# Schematic.net
KiCad netlist of a schematic drawn in Altium Designer
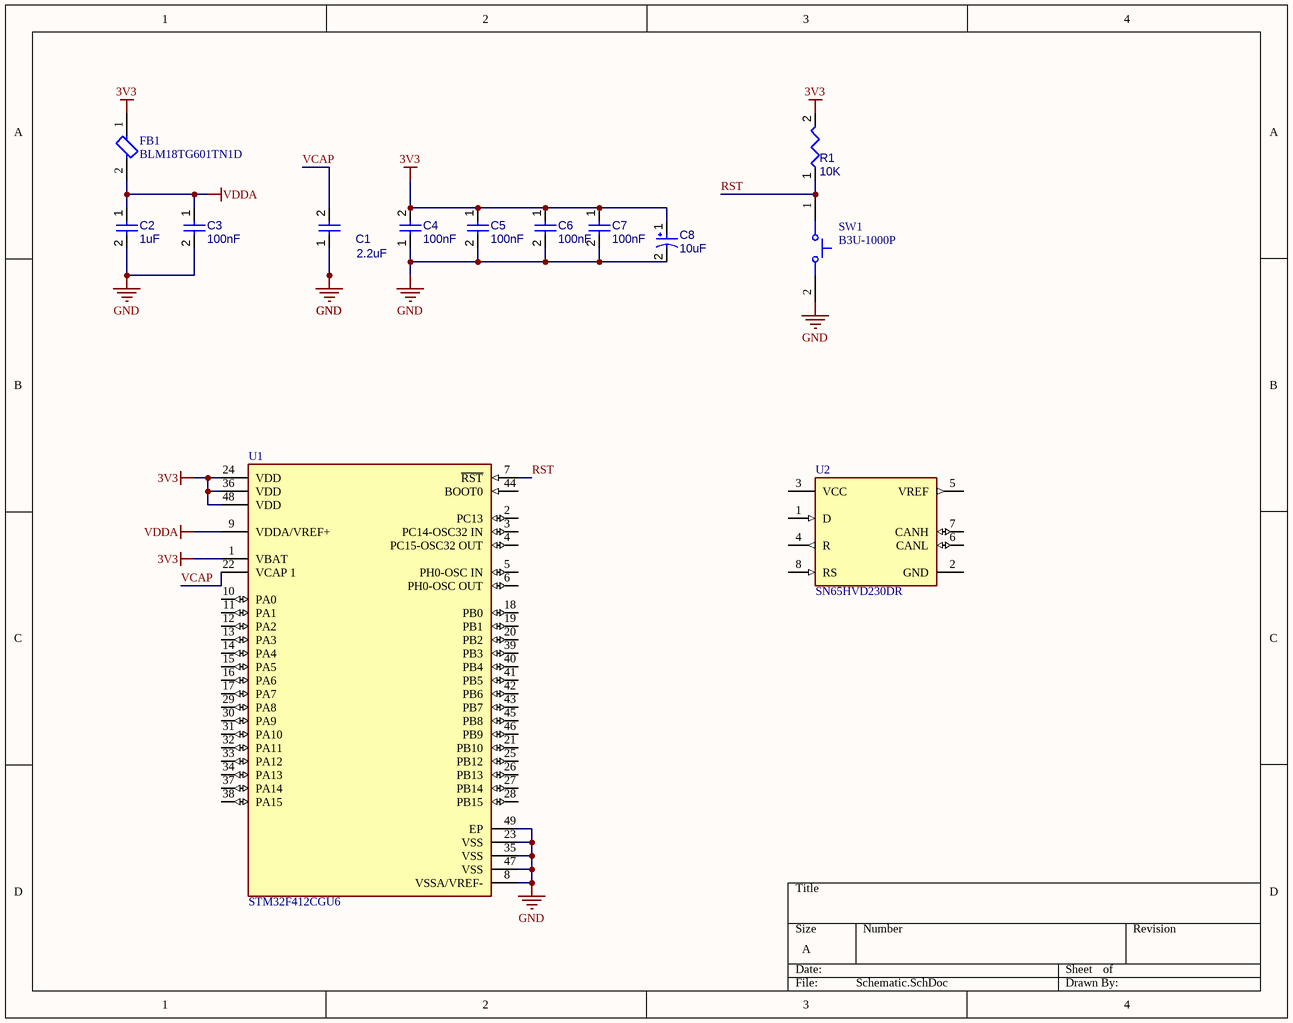
[diagram p0: Schematic.SchDoc]

(export (version "E")
  (design (tool "Eeschema 10.0.6"))
  (components
    (comp (ref "C1")
      (value "2.2uF")
      (footprint "CAPC0402(1005)60_L")
      (description "Chip Capacitor, 2,2µF +/-20%, 10V, 0402, Thickness 0.6 mm")
      (fields (field (name "TOLERANCE") "10%"))
      (libsource (lib "Bronco Racing") (part "CAP-NP-2"))
    )
    (comp (ref "C2")
      (value "1uF")
      (footprint "CAPC0402(1005)60_L")
      (description "Chip Capacitor, 1µF +/-20%, 10V, 0402, Thickness 0.6 mm")
      (fields (field (name "TOLERANCE") "10%"))
      (libsource (lib "Bronco Racing") (part "CAP-NP-2"))
    )
    (comp (ref "C3")
      (value "100nF")
      (footprint "CAPC0402(1005)60_L")
      (description "Chip Capacitor, 100nF +/-20%, 10V, 0402, Thickness 0.6 mm")
      (fields (field (name "TOLERANCE") "20%"))
      (libsource (lib "Bronco Racing") (part "CAP-NP-2"))
    )
    (comp (ref "C4")
      (value "100nF")
      (footprint "CAPC0402(1005)60_L")
      (description "Chip Capacitor, 100nF +/-20%, 10V, 0402, Thickness 0.6 mm")
      (fields (field (name "TOLERANCE") "20%"))
      (libsource (lib "Bronco Racing") (part "CAP-NP-2"))
    )
    (comp (ref "C5")
      (value "100nF")
      (footprint "CAPC0402(1005)60_L")
      (description "Chip Capacitor, 100nF +/-20%, 10V, 0402, Thickness 0.6 mm")
      (fields (field (name "TOLERANCE") "20%"))
      (libsource (lib "Bronco Racing") (part "CAP-NP-2"))
    )
    (comp (ref "C6")
      (value "100nF")
      (footprint "CAPC0402(1005)60_L")
      (description "Chip Capacitor, 100nF +/-20%, 10V, 0402, Thickness 0.6 mm")
      (fields (field (name "TOLERANCE") "20%"))
      (libsource (lib "Bronco Racing") (part "CAP-NP-2"))
    )
    (comp (ref "C7")
      (value "100nF")
      (footprint "CAPC0402(1005)60_L")
      (description "Chip Capacitor, 100nF +/-20%, 10V, 0402, Thickness 0.6 mm")
      (fields (field (name "TOLERANCE") "20%"))
      (libsource (lib "Bronco Racing") (part "CAP-NP-2"))
    )
    (comp (ref "C8")
      (value "10uF")
      (footprint "CAPMP3217X18-T_V")
      (description "Standard Tantalum, 10 uF, +/- 10%, 16 V, -55 to 125 degC, 1206 (3216 Metric), RoHS, Tape and Reel")
      (fields (field (name "TOLERANCE") "10%") (field (name "MANUFACTURER") "AVX"))
      (libsource (lib "Bronco Racing") (part "CAP-P-2"))
    )
    (comp (ref "FB1")
      (value "BLM18TG601TN1D")
      (footprint "FP-BLM18-0_15-0_1-t0_6-MFG")
      (description "FERRITE BEAD 600 OHM 0603 1LN")
      (fields (field (name "TOLERANCE") "25%"))
      (libsource (lib "Altium Content Vault") (part "5f30dd21d616792df468990f7003faa"))
    )
    (comp (ref "R1")
      (value "10K")
      (footprint "RESC0402(1005)_L")
      (description "Chip Resistor, 10 kOhms, +/-1 %, 63 mW, -55 to 125 degC, 0402")
      (fields (field (name "POWER") "63mW") (field (name "TOLERANCE") "1%"))
      (libsource (lib "Bronco Racing") (part "RES-2"))
    )
    (comp (ref "SW1")
      (value "B3U-1000P")
      (footprint "OMRON-B3U-1000_V")
      (description "Tactile Switch, SPST-NO, 0.05 A, 12 V, -25 to 70 degC, 2-Pin SMD, RoHS, Tape and Reel")
      (fields (field (name "MANUFACTURER") "Omron Electronic Components"))
      (libsource (lib "Bronco Racing") (part "SW-SPST-NO-2"))
    )
    (comp (ref "U1")
      (value "STM32F412CGU6")
      (footprint "FP-UFQFPN48-A0B9-MFG")
      (description "IC MCU 32BIT 1MB FLASH 48UFQFPN")
      (libsource (lib "Altium Content Vault") (part "7dd92b861eb4b166e7106aa1111722c"))
    )
    (comp (ref "U2")
      (value "SN65HVD230DR")
      (footprint "FP-D0008A-IPC_A")
      (description "IC TRANSCEIVER HALF 1/1 8SOIC")
      (libsource (lib "Altium Content Vault") (part "43b56812b1adf0e60a7acfb7c27ab91"))
    )
  )
  (nets
    (net (code "1") (name "/RST") (class "Default")
      (node (ref "R1") (pin "1") (pinfunction "1_1") (pintype "passive"))
      (node (ref "SW1") (pin "1") (pinfunction "1_1") (pintype "passive"))
      (node (ref "U1") (pin "7") (pinfunction "~{RST}_7") (pintype "input"))
    )
    (net (code "2") (name "/VCAP") (class "Default")
      (node (ref "C1") (pin "2") (pinfunction "2_2") (pintype "passive"))
      (node (ref "U1") (pin "22") (pinfunction "VCAP_1_22") (pintype "power_in"))
    )
    (net (code "3") (name "3V3") (class "Default")
      (node (ref "C4") (pin "2") (pinfunction "2_2") (pintype "passive"))
      (node (ref "C5") (pin "1") (pinfunction "1_1") (pintype "passive"))
      (node (ref "C6") (pin "1") (pinfunction "1_1") (pintype "passive"))
      (node (ref "C7") (pin "1") (pinfunction "1_1") (pintype "passive"))
      (node (ref "C8") (pin "1") (pinfunction "1_1") (pintype "passive"))
      (node (ref "FB1") (pin "1") (pinfunction "1_1") (pintype "passive"))
      (node (ref "R1") (pin "2") (pinfunction "2_2") (pintype "passive"))
      (node (ref "U1") (pin "1") (pinfunction "VBAT_1") (pintype "power_in"))
      (node (ref "U1") (pin "24") (pinfunction "VDD_24") (pintype "power_in"))
      (node (ref "U1") (pin "36") (pinfunction "VDD_36") (pintype "power_in"))
      (node (ref "U1") (pin "48") (pinfunction "VDD_48") (pintype "power_in"))
    )
    (net (code "4") (name "GND") (class "Default")
      (node (ref "C1") (pin "1") (pinfunction "1_1") (pintype "passive"))
      (node (ref "C2") (pin "2") (pinfunction "2_2") (pintype "passive"))
      (node (ref "C3") (pin "2") (pinfunction "2_2") (pintype "passive"))
      (node (ref "C4") (pin "1") (pinfunction "1_1") (pintype "passive"))
      (node (ref "C5") (pin "2") (pinfunction "2_2") (pintype "passive"))
      (node (ref "C6") (pin "2") (pinfunction "2_2") (pintype "passive"))
      (node (ref "C7") (pin "2") (pinfunction "2_2") (pintype "passive"))
      (node (ref "C8") (pin "2") (pinfunction "2_2") (pintype "passive"))
      (node (ref "SW1") (pin "2") (pinfunction "2_2") (pintype "passive"))
      (node (ref "U1") (pin "23") (pinfunction "VSS_23") (pintype "power_in"))
      (node (ref "U1") (pin "35") (pinfunction "VSS_35") (pintype "power_in"))
      (node (ref "U1") (pin "47") (pinfunction "VSS_47") (pintype "power_in"))
      (node (ref "U1") (pin "49") (pinfunction "EP_49") (pintype "passive"))
      (node (ref "U1") (pin "8") (pinfunction "VSSA/VREF-_8") (pintype "power_in"))
    )
    (net (code "5") (name "VDDA") (class "Default")
      (node (ref "C2") (pin "1") (pinfunction "1_1") (pintype "passive"))
      (node (ref "C3") (pin "1") (pinfunction "1_1") (pintype "passive"))
      (node (ref "FB1") (pin "2") (pinfunction "2_2") (pintype "passive"))
      (node (ref "U1") (pin "9") (pinfunction "VDDA/VREF+_9") (pintype "power_in"))
    )
    (net (code "6") (name "unconnected-(U1-BOOT0-Pad44)") (class "Default")
      (node (ref "U1") (pin "44") (pinfunction "BOOT0_44") (pintype "input"))
    )
    (net (code "7") (name "unconnected-(U1-PA0-Pad10)") (class "Default")
      (node (ref "U1") (pin "10") (pinfunction "PA0_10") (pintype "bidirectional"))
    )
    (net (code "8") (name "unconnected-(U1-PA1-Pad11)") (class "Default")
      (node (ref "U1") (pin "11") (pinfunction "PA1_11") (pintype "bidirectional"))
    )
    (net (code "9") (name "unconnected-(U1-PA2-Pad12)") (class "Default")
      (node (ref "U1") (pin "12") (pinfunction "PA2_12") (pintype "bidirectional"))
    )
    (net (code "10") (name "unconnected-(U1-PA3-Pad13)") (class "Default")
      (node (ref "U1") (pin "13") (pinfunction "PA3_13") (pintype "bidirectional"))
    )
    (net (code "11") (name "unconnected-(U1-PA4-Pad14)") (class "Default")
      (node (ref "U1") (pin "14") (pinfunction "PA4_14") (pintype "bidirectional"))
    )
    (net (code "12") (name "unconnected-(U1-PA5-Pad15)") (class "Default")
      (node (ref "U1") (pin "15") (pinfunction "PA5_15") (pintype "bidirectional"))
    )
    (net (code "13") (name "unconnected-(U1-PA6-Pad16)") (class "Default")
      (node (ref "U1") (pin "16") (pinfunction "PA6_16") (pintype "bidirectional"))
    )
    (net (code "14") (name "unconnected-(U1-PA7-Pad17)") (class "Default")
      (node (ref "U1") (pin "17") (pinfunction "PA7_17") (pintype "bidirectional"))
    )
    (net (code "15") (name "unconnected-(U1-PA8-Pad29)") (class "Default")
      (node (ref "U1") (pin "29") (pinfunction "PA8_29") (pintype "bidirectional"))
    )
    (net (code "16") (name "unconnected-(U1-PA9-Pad30)") (class "Default")
      (node (ref "U1") (pin "30") (pinfunction "PA9_30") (pintype "bidirectional"))
    )
    (net (code "17") (name "unconnected-(U1-PA10-Pad31)") (class "Default")
      (node (ref "U1") (pin "31") (pinfunction "PA10_31") (pintype "bidirectional"))
    )
    (net (code "18") (name "unconnected-(U1-PA11-Pad32)") (class "Default")
      (node (ref "U1") (pin "32") (pinfunction "PA11_32") (pintype "bidirectional"))
    )
    (net (code "19") (name "unconnected-(U1-PA12-Pad33)") (class "Default")
      (node (ref "U1") (pin "33") (pinfunction "PA12_33") (pintype "bidirectional"))
    )
    (net (code "20") (name "unconnected-(U1-PA13-Pad34)") (class "Default")
      (node (ref "U1") (pin "34") (pinfunction "PA13_34") (pintype "bidirectional"))
    )
    (net (code "21") (name "unconnected-(U1-PA14-Pad37)") (class "Default")
      (node (ref "U1") (pin "37") (pinfunction "PA14_37") (pintype "bidirectional"))
    )
    (net (code "22") (name "unconnected-(U1-PA15-Pad38)") (class "Default")
      (node (ref "U1") (pin "38") (pinfunction "PA15_38") (pintype "bidirectional"))
    )
    (net (code "23") (name "unconnected-(U1-PB0-Pad18)") (class "Default")
      (node (ref "U1") (pin "18") (pinfunction "PB0_18") (pintype "bidirectional"))
    )
    (net (code "24") (name "unconnected-(U1-PB1-Pad19)") (class "Default")
      (node (ref "U1") (pin "19") (pinfunction "PB1_19") (pintype "bidirectional"))
    )
    (net (code "25") (name "unconnected-(U1-PB2-Pad20)") (class "Default")
      (node (ref "U1") (pin "20") (pinfunction "PB2_20") (pintype "bidirectional"))
    )
    (net (code "26") (name "unconnected-(U1-PB3-Pad39)") (class "Default")
      (node (ref "U1") (pin "39") (pinfunction "PB3_39") (pintype "bidirectional"))
    )
    (net (code "27") (name "unconnected-(U1-PB4-Pad40)") (class "Default")
      (node (ref "U1") (pin "40") (pinfunction "PB4_40") (pintype "bidirectional"))
    )
    (net (code "28") (name "unconnected-(U1-PB5-Pad41)") (class "Default")
      (node (ref "U1") (pin "41") (pinfunction "PB5_41") (pintype "bidirectional"))
    )
    (net (code "29") (name "unconnected-(U1-PB6-Pad42)") (class "Default")
      (node (ref "U1") (pin "42") (pinfunction "PB6_42") (pintype "bidirectional"))
    )
    (net (code "30") (name "unconnected-(U1-PB7-Pad43)") (class "Default")
      (node (ref "U1") (pin "43") (pinfunction "PB7_43") (pintype "bidirectional"))
    )
    (net (code "31") (name "unconnected-(U1-PB8-Pad45)") (class "Default")
      (node (ref "U1") (pin "45") (pinfunction "PB8_45") (pintype "bidirectional"))
    )
    (net (code "32") (name "unconnected-(U1-PB9-Pad46)") (class "Default")
      (node (ref "U1") (pin "46") (pinfunction "PB9_46") (pintype "bidirectional"))
    )
    (net (code "33") (name "unconnected-(U1-PB10-Pad21)") (class "Default")
      (node (ref "U1") (pin "21") (pinfunction "PB10_21") (pintype "bidirectional"))
    )
    (net (code "34") (name "unconnected-(U1-PB12-Pad25)") (class "Default")
      (node (ref "U1") (pin "25") (pinfunction "PB12_25") (pintype "bidirectional"))
    )
    (net (code "35") (name "unconnected-(U1-PB13-Pad26)") (class "Default")
      (node (ref "U1") (pin "26") (pinfunction "PB13_26") (pintype "bidirectional"))
    )
    (net (code "36") (name "unconnected-(U1-PB14-Pad27)") (class "Default")
      (node (ref "U1") (pin "27") (pinfunction "PB14_27") (pintype "bidirectional"))
    )
    (net (code "37") (name "unconnected-(U1-PB15-Pad28)") (class "Default")
      (node (ref "U1") (pin "28") (pinfunction "PB15_28") (pintype "bidirectional"))
    )
    (net (code "38") (name "unconnected-(U1-PC13-Pad2)") (class "Default")
      (node (ref "U1") (pin "2") (pinfunction "PC13_2") (pintype "bidirectional"))
    )
    (net (code "39") (name "unconnected-(U1-PC14-OSC32_IN-Pad3)") (class "Default")
      (node (ref "U1") (pin "3") (pinfunction "PC14-OSC32_IN_3") (pintype "bidirectional"))
    )
    (net (code "40") (name "unconnected-(U1-PC15-OSC32_OUT-Pad4)") (class "Default")
      (node (ref "U1") (pin "4") (pinfunction "PC15-OSC32_OUT_4") (pintype "bidirectional"))
    )
    (net (code "41") (name "unconnected-(U1-PH0-OSC_IN-Pad5)") (class "Default")
      (node (ref "U1") (pin "5") (pinfunction "PH0-OSC_IN_5") (pintype "bidirectional"))
    )
    (net (code "42") (name "unconnected-(U1-PH0-OSC_OUT-Pad6)") (class "Default")
      (node (ref "U1") (pin "6") (pinfunction "PH0-OSC_OUT_6") (pintype "bidirectional"))
    )
    (net (code "43") (name "unconnected-(U2-CANH-Pad7)") (class "Default")
      (node (ref "U2") (pin "7") (pinfunction "CANH_7") (pintype "bidirectional"))
    )
    (net (code "44") (name "unconnected-(U2-CANL-Pad6)") (class "Default")
      (node (ref "U2") (pin "6") (pinfunction "CANL_6") (pintype "bidirectional"))
    )
    (net (code "45") (name "unconnected-(U2-D-Pad1)") (class "Default")
      (node (ref "U2") (pin "1") (pinfunction "D_1") (pintype "input"))
    )
    (net (code "46") (name "unconnected-(U2-GND-Pad2)") (class "Default")
      (node (ref "U2") (pin "2") (pinfunction "GND_2") (pintype "power_in"))
    )
    (net (code "47") (name "unconnected-(U2-R-Pad4)") (class "Default")
      (node (ref "U2") (pin "4") (pinfunction "R_4") (pintype "output"))
    )
    (net (code "48") (name "unconnected-(U2-RS-Pad8)") (class "Default")
      (node (ref "U2") (pin "8") (pinfunction "RS_8") (pintype "input"))
    )
    (net (code "49") (name "unconnected-(U2-VCC-Pad3)") (class "Default")
      (node (ref "U2") (pin "3") (pinfunction "VCC_3") (pintype "power_in"))
    )
    (net (code "50") (name "unconnected-(U2-VREF-Pad5)") (class "Default")
      (node (ref "U2") (pin "5") (pinfunction "VREF_5") (pintype "output"))
    )
  )
)
